# untitled.net
KiCad netlist of a schematic drawn in EAGLE
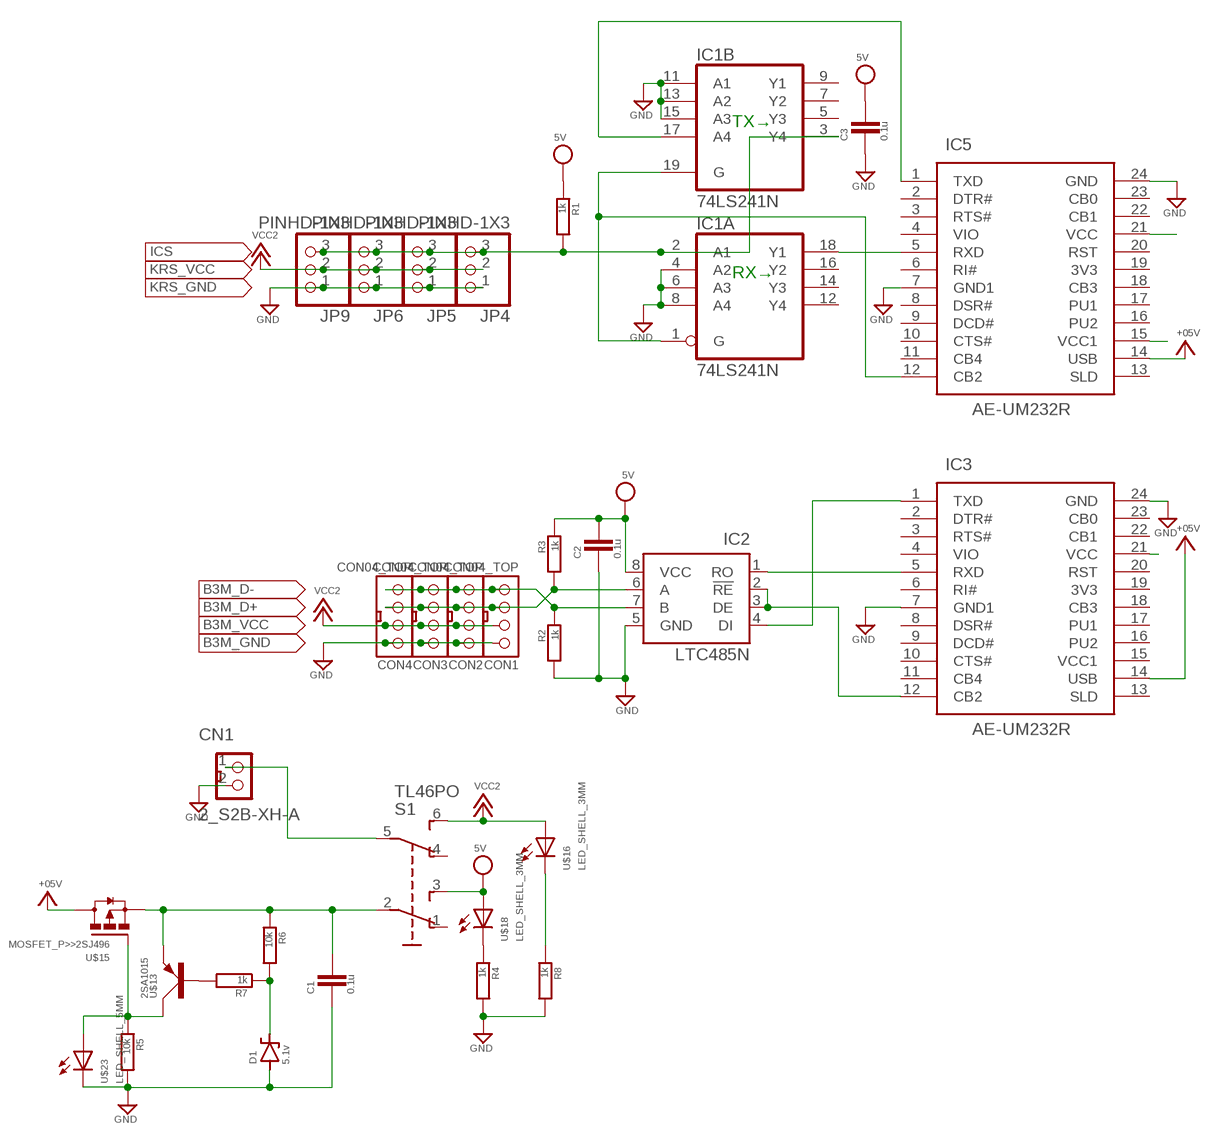
[diagram p0: schematic, sheet 1]

(export (version "E")
  (design (tool "Eeschema 10.0.6"))
  (components
    (comp (ref "C1")
      (value "0.1u")
      (footprint "eagle-import:C050-024X044")
      (libsource (lib "eagle-import") (part "C{gt}{gt}050-024X044"))
    )
    (comp (ref "C2")
      (value "0.1u")
      (footprint "eagle-import:C050-024X044")
      (libsource (lib "eagle-import") (part "C{gt}{gt}050-024X044"))
    )
    (comp (ref "C3")
      (value "0.1u")
      (footprint "eagle-import:C050-024X044")
      (libsource (lib "eagle-import") (part "C{gt}{gt}050-024X044"))
    )
    (comp (ref "CN1")
      (value "2_S2B-XH-A")
      (footprint "eagle-import:S2B-XH-A")
      (libsource (lib "eagle-import") (part "2_S2B-XH-A"))
    )
    (comp (ref "CON1")
      (value "CON04_TOP")
      (footprint "eagle-import:TOP_CON4")
      (libsource (lib "eagle-import") (part "CON04_TOP"))
    )
    (comp (ref "CON2")
      (value "CON04_TOP")
      (footprint "eagle-import:TOP_CON4")
      (libsource (lib "eagle-import") (part "CON04_TOP"))
    )
    (comp (ref "CON3")
      (value "CON04_TOP")
      (footprint "eagle-import:TOP_CON4")
      (libsource (lib "eagle-import") (part "CON04_TOP"))
    )
    (comp (ref "CON4")
      (value "CON04_TOP")
      (footprint "eagle-import:TOP_CON4")
      (libsource (lib "eagle-import") (part "CON04_TOP"))
    )
    (comp (ref "D1")
      (value "5.1v")
      (footprint "eagle-import:ZDIO-5")
      (libsource (lib "eagle-import") (part "ZENER-DIODE{gt}{gt}ZD-5"))
    )
    (comp (ref "IC1")
      (value "74LS241N")
      (footprint "eagle-import:DIL20")
      (libsource (lib "eagle-import") (part "74241NLS"))
    )
    (comp (ref "IC2")
      (value "LTC485N")
      (footprint "eagle-import:DIL08")
      (libsource (lib "eagle-import") (part "LTC485N"))
    )
    (comp (ref "IC3")
      (value "AE-UM232R")
      (footprint "eagle-import:AE-UM232R")
      (libsource (lib "eagle-import") (part "AE-UM232R"))
    )
    (comp (ref "IC5")
      (value "AE-UM232R")
      (footprint "eagle-import:AE-UM232R")
      (libsource (lib "eagle-import") (part "AE-UM232R"))
    )
    (comp (ref "JP4")
      (value "PINHD-1X3")
      (footprint "eagle-import:1X03")
      (libsource (lib "eagle-import") (part "PINHD-1X3"))
    )
    (comp (ref "JP5")
      (value "PINHD-1X3")
      (footprint "eagle-import:1X03")
      (libsource (lib "eagle-import") (part "PINHD-1X3"))
    )
    (comp (ref "JP6")
      (value "PINHD-1X3")
      (footprint "eagle-import:1X03")
      (libsource (lib "eagle-import") (part "PINHD-1X3"))
    )
    (comp (ref "JP9")
      (value "PINHD-1X3")
      (footprint "eagle-import:1X03")
      (libsource (lib "eagle-import") (part "PINHD-1X3"))
    )
    (comp (ref "R1")
      (value "1k")
      (footprint "eagle-import:1_4W(8MM)")
      (libsource (lib "eagle-import") (part "R-EU{gt}{gt}1/4W(8MM)"))
    )
    (comp (ref "R2")
      (value "1k")
      (footprint "eagle-import:1_4W(8MM)")
      (libsource (lib "eagle-import") (part "R-EU{gt}{gt}1/4W(8MM)"))
    )
    (comp (ref "R3")
      (value "1k")
      (footprint "eagle-import:1_4W(8MM)")
      (libsource (lib "eagle-import") (part "R-EU{gt}{gt}1/4W(8MM)"))
    )
    (comp (ref "R4")
      (value "1k")
      (footprint "eagle-import:1_4W(8MM)")
      (libsource (lib "eagle-import") (part "R-EU{gt}{gt}1/4W(8MM)"))
    )
    (comp (ref "R5")
      (value "10k")
      (footprint "eagle-import:1_4W(8MM)")
      (libsource (lib "eagle-import") (part "R-EU{gt}{gt}1/4W(8MM)"))
    )
    (comp (ref "R6")
      (value "10k")
      (footprint "eagle-import:1_4W(8MM)")
      (libsource (lib "eagle-import") (part "R-EU{gt}{gt}1/4W(8MM)"))
    )
    (comp (ref "R7")
      (value "1k")
      (footprint "eagle-import:1_4W(8MM)")
      (libsource (lib "eagle-import") (part "R-EU{gt}{gt}1/4W(8MM)"))
    )
    (comp (ref "R8")
      (value "1k")
      (footprint "eagle-import:1_4W(8MM)")
      (libsource (lib "eagle-import") (part "R-EU{gt}{gt}1/4W(8MM)"))
    )
    (comp (ref "S1")
      (value "TL46PO")
      (footprint "eagle-import:TL4XPO")
      (libsource (lib "eagle-import") (part "TL46PO"))
    )
    (comp (ref "U$13")
      (value "2SA1015")
      (footprint "eagle-import:TO-92")
      (libsource (lib "eagle-import") (part "TR_PNP{gt}{gt}TO-92"))
    )
    (comp (ref "U$15")
      (value "MOSFET_P>>2SJ496")
      (footprint "eagle-import:TO-92")
      (libsource (lib "eagle-import") (part "MOSFET_P{gt}{gt}2SJ496"))
    )
    (comp (ref "U$16")
      (value "LED_SHELL_3MM")
      (footprint "eagle-import:3MM")
      (libsource (lib "eagle-import") (part "LED_SHELL_3MM"))
    )
    (comp (ref "U$18")
      (value "LED_SHELL_3MM")
      (footprint "eagle-import:3MM")
      (libsource (lib "eagle-import") (part "LED_SHELL_3MM"))
    )
    (comp (ref "U$23")
      (value "LED_SHELL_5MM")
      (footprint "eagle-import:5MM")
      (libsource (lib "eagle-import") (part "LED_SHELL_5MM"))
    )
  )
  (nets
    (net (code "1") (name "+05V") (class "Default")
      (node (ref "IC3") (pin "14") (pinfunction "USB_14") (pintype "bidirectional"))
      (node (ref "IC5") (pin "14") (pinfunction "USB_14") (pintype "bidirectional"))
      (node (ref "U$15") (pin "2") (pinfunction "D_2") (pintype "passive"))
    )
    (net (code "2") (name "/VCC1") (class "Default")
      (node (ref "IC3") (pin "15") (pinfunction "VCC1_15") (pintype "power_in"))
    )
    (net (code "3") (name "5V") (class "Default")
      (node (ref "C2") (pin "1") (pinfunction "1_1") (pintype "passive"))
      (node (ref "C3") (pin "1") (pinfunction "1_1") (pintype "passive"))
      (node (ref "IC2") (pin "8") (pinfunction "VCC_8") (pintype "input"))
      (node (ref "R1") (pin "1") (pinfunction "1_1") (pintype "passive"))
      (node (ref "R3") (pin "1") (pinfunction "1_1") (pintype "passive"))
      (node (ref "S1") (pin "3") (pinfunction "S_3") (pintype "passive"))
      (node (ref "U$18") (pin "P$1") (pinfunction "A_P$1") (pintype "passive"))
    )
    (net (code "4") (name "GND") (class "Default")
      (node (ref "C1") (pin "2") (pinfunction "2_2") (pintype "passive"))
      (node (ref "C2") (pin "2") (pinfunction "2_2") (pintype "passive"))
      (node (ref "C3") (pin "2") (pinfunction "2_2") (pintype "passive"))
      (node (ref "CN1") (pin "2") (pinfunction "2_2") (pintype "passive"))
      (node (ref "CON1") (pin "P$1") (pinfunction "1_P$1") (pintype "bidirectional"))
      (node (ref "CON2") (pin "P$1") (pinfunction "1_P$1") (pintype "bidirectional"))
      (node (ref "CON3") (pin "P$1") (pinfunction "1_P$1") (pintype "bidirectional"))
      (node (ref "CON4") (pin "P$1") (pinfunction "1_P$1") (pintype "bidirectional"))
      (node (ref "D1") (pin "A") (pinfunction "A_A") (pintype "passive"))
      (node (ref "IC1") (pin "11") (pinfunction "A1_11") (pintype "input"))
      (node (ref "IC1") (pin "13") (pinfunction "A2_13") (pintype "input"))
      (node (ref "IC1") (pin "15") (pinfunction "A3_15") (pintype "input"))
      (node (ref "IC1") (pin "4") (pinfunction "A2_4") (pintype "input"))
      (node (ref "IC1") (pin "6") (pinfunction "A3_6") (pintype "input"))
      (node (ref "IC1") (pin "8") (pinfunction "A4_8") (pintype "input"))
      (node (ref "IC2") (pin "5") (pinfunction "GND_5") (pintype "input"))
      (node (ref "IC3") (pin "24") (pinfunction "GND_24") (pintype "power_in"))
      (node (ref "IC3") (pin "7") (pinfunction "GND1_7") (pintype "power_in"))
      (node (ref "IC5") (pin "24") (pinfunction "GND_24") (pintype "power_in"))
      (node (ref "IC5") (pin "7") (pinfunction "GND1_7") (pintype "power_in"))
      (node (ref "JP4") (pin "1") (pinfunction "1_1") (pintype "passive"))
      (node (ref "JP5") (pin "1") (pinfunction "1_1") (pintype "passive"))
      (node (ref "JP6") (pin "1") (pinfunction "1_1") (pintype "passive"))
      (node (ref "JP9") (pin "1") (pinfunction "1_1") (pintype "passive"))
      (node (ref "R2") (pin "2") (pinfunction "2_2") (pintype "passive"))
      (node (ref "R4") (pin "2") (pinfunction "2_2") (pintype "passive"))
      (node (ref "R5") (pin "2") (pinfunction "2_2") (pintype "passive"))
      (node (ref "R8") (pin "2") (pinfunction "2_2") (pintype "passive"))
      (node (ref "U$23") (pin "P$2") (pinfunction "C_P$2") (pintype "passive"))
    )
    (net (code "5") (name "Net-(CON1-3)") (class "Default")
      (node (ref "CON1") (pin "P$3") (pinfunction "3_P$3") (pintype "bidirectional"))
      (node (ref "CON2") (pin "P$3") (pinfunction "3_P$3") (pintype "bidirectional"))
      (node (ref "CON3") (pin "P$3") (pinfunction "3_P$3") (pintype "bidirectional"))
      (node (ref "CON4") (pin "P$3") (pinfunction "3_P$3") (pintype "bidirectional"))
      (node (ref "IC2") (pin "6") (pinfunction "A_6") (pintype "bidirectional"))
      (node (ref "R3") (pin "2") (pinfunction "2_2") (pintype "passive"))
    )
    (net (code "6") (name "Net-(CON1-4)") (class "Default")
      (node (ref "CON1") (pin "P$4") (pinfunction "4_P$4") (pintype "bidirectional"))
      (node (ref "CON2") (pin "P$4") (pinfunction "4_P$4") (pintype "bidirectional"))
      (node (ref "CON3") (pin "P$4") (pinfunction "4_P$4") (pintype "bidirectional"))
      (node (ref "CON4") (pin "P$4") (pinfunction "4_P$4") (pintype "bidirectional"))
      (node (ref "IC2") (pin "7") (pinfunction "B_7") (pintype "bidirectional"))
      (node (ref "R2") (pin "1") (pinfunction "1_1") (pintype "passive"))
    )
    (net (code "7") (name "Net-(D1-PadC)") (class "Default")
      (node (ref "D1") (pin "C") (pinfunction "C_C") (pintype "passive"))
      (node (ref "R6") (pin "2") (pinfunction "2_2") (pintype "passive"))
      (node (ref "R7") (pin "1") (pinfunction "1_1") (pintype "passive"))
    )
    (net (code "8") (name "Net-(IC1A-A1)") (class "Default")
      (node (ref "IC1") (pin "2") (pinfunction "A1_2") (pintype "input"))
      (node (ref "IC1") (pin "3") (pinfunction "Y4_3") (pintype "tri_state"))
      (node (ref "JP4") (pin "3") (pinfunction "3_3") (pintype "passive"))
      (node (ref "JP5") (pin "3") (pinfunction "3_3") (pintype "passive"))
      (node (ref "JP6") (pin "3") (pinfunction "3_3") (pintype "passive"))
      (node (ref "JP9") (pin "3") (pinfunction "3_3") (pintype "passive"))
      (node (ref "R1") (pin "2") (pinfunction "2_2") (pintype "passive"))
    )
    (net (code "9") (name "Net-(IC1A-G)") (class "Default")
      (node (ref "IC1") (pin "1") (pinfunction "G_1") (pintype "input"))
      (node (ref "IC1") (pin "19") (pinfunction "G_19") (pintype "input"))
      (node (ref "IC5") (pin "12") (pinfunction "CB2_12") (pintype "bidirectional"))
    )
    (net (code "10") (name "Net-(IC1A-Y1)") (class "Default")
      (node (ref "IC1") (pin "18") (pinfunction "Y1_18") (pintype "tri_state"))
      (node (ref "IC5") (pin "5") (pinfunction "RXD_5") (pintype "bidirectional"))
    )
    (net (code "11") (name "Net-(IC1B-A4)") (class "Default")
      (node (ref "IC1") (pin "17") (pinfunction "A4_17") (pintype "input"))
      (node (ref "IC5") (pin "1") (pinfunction "TXD_1") (pintype "bidirectional"))
    )
    (net (code "12") (name "Net-(IC2-DE)") (class "Default")
      (node (ref "IC2") (pin "2") (pinfunction "~{RE}_2") (pintype "input"))
      (node (ref "IC2") (pin "3") (pinfunction "DE_3") (pintype "input"))
      (node (ref "IC3") (pin "12") (pinfunction "CB2_12") (pintype "bidirectional"))
    )
    (net (code "13") (name "Net-(IC2-DI)") (class "Default")
      (node (ref "IC2") (pin "4") (pinfunction "DI_4") (pintype "input"))
      (node (ref "IC3") (pin "1") (pinfunction "TXD_1") (pintype "bidirectional"))
    )
    (net (code "14") (name "Net-(IC2-RO)") (class "Default")
      (node (ref "IC2") (pin "1") (pinfunction "RO_1") (pintype "output"))
      (node (ref "IC3") (pin "5") (pinfunction "RXD_5") (pintype "bidirectional"))
    )
    (net (code "15") (name "Net-(S1-P)") (class "Default")
      (node (ref "C1") (pin "1") (pinfunction "1_1") (pintype "passive"))
      (node (ref "R6") (pin "1") (pinfunction "1_1") (pintype "passive"))
      (node (ref "S1") (pin "2") (pinfunction "P_2") (pintype "passive"))
      (node (ref "U$13") (pin "1") (pinfunction "E_1") (pintype "passive"))
      (node (ref "U$15") (pin "1") (pinfunction "S_1") (pintype "passive"))
    )
    (net (code "16") (name "Net-(S1-P1)") (class "Default")
      (node (ref "CN1") (pin "1") (pinfunction "1_1") (pintype "passive"))
      (node (ref "S1") (pin "5") (pinfunction "P1_5") (pintype "passive"))
    )
    (net (code "17") (name "Net-(U$13-B)") (class "Default")
      (node (ref "R7") (pin "2") (pinfunction "2_2") (pintype "passive"))
      (node (ref "U$13") (pin "3") (pinfunction "B_3") (pintype "passive"))
    )
    (net (code "18") (name "Net-(U$13-C)") (class "Default")
      (node (ref "R5") (pin "1") (pinfunction "1_1") (pintype "passive"))
      (node (ref "U$13") (pin "2") (pinfunction "C_2") (pintype "passive"))
      (node (ref "U$15") (pin "3") (pinfunction "G_3") (pintype "passive"))
      (node (ref "U$23") (pin "P$1") (pinfunction "A_P$1") (pintype "passive"))
    )
    (net (code "19") (name "Net-(U$16-C)") (class "Default")
      (node (ref "R8") (pin "1") (pinfunction "1_1") (pintype "passive"))
      (node (ref "U$16") (pin "P$2") (pinfunction "C_P$2") (pintype "passive"))
    )
    (net (code "20") (name "Net-(U$18-C)") (class "Default")
      (node (ref "R4") (pin "1") (pinfunction "1_1") (pintype "passive"))
      (node (ref "U$18") (pin "P$2") (pinfunction "C_P$2") (pintype "passive"))
    )
    (net (code "21") (name "VCC2") (class "Default")
      (node (ref "CON1") (pin "P$2") (pinfunction "2_P$2") (pintype "bidirectional"))
      (node (ref "CON2") (pin "P$2") (pinfunction "2_P$2") (pintype "bidirectional"))
      (node (ref "CON3") (pin "P$2") (pinfunction "2_P$2") (pintype "bidirectional"))
      (node (ref "CON4") (pin "P$2") (pinfunction "2_P$2") (pintype "bidirectional"))
      (node (ref "JP4") (pin "2") (pinfunction "2_2") (pintype "passive"))
      (node (ref "JP5") (pin "2") (pinfunction "2_2") (pintype "passive"))
      (node (ref "JP6") (pin "2") (pinfunction "2_2") (pintype "passive"))
      (node (ref "JP9") (pin "2") (pinfunction "2_2") (pintype "passive"))
      (node (ref "S1") (pin "6") (pinfunction "S1_6") (pintype "passive"))
      (node (ref "U$16") (pin "P$1") (pinfunction "A_P$1") (pintype "passive"))
    )
    (net (code "22") (name "unconnected-(IC1A-Y2-Pad16)") (class "Default")
      (node (ref "IC1") (pin "16") (pinfunction "Y2_16") (pintype "tri_state"))
    )
    (net (code "23") (name "unconnected-(IC1A-Y3-Pad14)") (class "Default")
      (node (ref "IC1") (pin "14") (pinfunction "Y3_14") (pintype "tri_state"))
    )
    (net (code "24") (name "unconnected-(IC1A-Y4-Pad12)") (class "Default")
      (node (ref "IC1") (pin "12") (pinfunction "Y4_12") (pintype "tri_state"))
    )
    (net (code "25") (name "unconnected-(IC1B-Y1-Pad9)") (class "Default")
      (node (ref "IC1") (pin "9") (pinfunction "Y1_9") (pintype "tri_state"))
    )
    (net (code "26") (name "unconnected-(IC1B-Y2-Pad7)") (class "Default")
      (node (ref "IC1") (pin "7") (pinfunction "Y2_7") (pintype "tri_state"))
    )
    (net (code "27") (name "unconnected-(IC1B-Y3-Pad5)") (class "Default")
      (node (ref "IC1") (pin "5") (pinfunction "Y3_5") (pintype "tri_state"))
    )
    (net (code "28") (name "unconnected-(IC3-3V3-Pad19)") (class "Default")
      (node (ref "IC3") (pin "19") (pinfunction "3V3_19") (pintype "bidirectional"))
    )
    (net (code "29") (name "unconnected-(IC3-CB0-Pad23)") (class "Default")
      (node (ref "IC3") (pin "23") (pinfunction "CB0_23") (pintype "bidirectional"))
    )
    (net (code "30") (name "unconnected-(IC3-CB1-Pad22)") (class "Default")
      (node (ref "IC3") (pin "22") (pinfunction "CB1_22") (pintype "bidirectional"))
    )
    (net (code "31") (name "unconnected-(IC3-CB3-Pad18)") (class "Default")
      (node (ref "IC3") (pin "18") (pinfunction "CB3_18") (pintype "bidirectional"))
    )
    (net (code "32") (name "unconnected-(IC3-CB4-Pad11)") (class "Default")
      (node (ref "IC3") (pin "11") (pinfunction "CB4_11") (pintype "bidirectional"))
    )
    (net (code "33") (name "unconnected-(IC3-CTS#-Pad10)") (class "Default")
      (node (ref "IC3") (pin "10") (pinfunction "CTS#_10") (pintype "bidirectional"))
    )
    (net (code "34") (name "unconnected-(IC3-DCD#-Pad9)") (class "Default")
      (node (ref "IC3") (pin "9") (pinfunction "DCD#_9") (pintype "bidirectional"))
    )
    (net (code "35") (name "unconnected-(IC3-DSR#-Pad8)") (class "Default")
      (node (ref "IC3") (pin "8") (pinfunction "DSR#_8") (pintype "bidirectional"))
    )
    (net (code "36") (name "unconnected-(IC3-DTR#-Pad2)") (class "Default")
      (node (ref "IC3") (pin "2") (pinfunction "DTR#_2") (pintype "bidirectional"))
    )
    (net (code "37") (name "unconnected-(IC3-PU1-Pad17)") (class "Default")
      (node (ref "IC3") (pin "17") (pinfunction "PU1_17") (pintype "bidirectional"))
    )
    (net (code "38") (name "unconnected-(IC3-PU2-Pad16)") (class "Default")
      (node (ref "IC3") (pin "16") (pinfunction "PU2_16") (pintype "bidirectional"))
    )
    (net (code "39") (name "unconnected-(IC3-RI#-Pad6)") (class "Default")
      (node (ref "IC3") (pin "6") (pinfunction "RI#_6") (pintype "bidirectional"))
    )
    (net (code "40") (name "unconnected-(IC3-RST-Pad20)") (class "Default")
      (node (ref "IC3") (pin "20") (pinfunction "RST_20") (pintype "bidirectional"))
    )
    (net (code "41") (name "unconnected-(IC3-RTS#-Pad3)") (class "Default")
      (node (ref "IC3") (pin "3") (pinfunction "RTS#_3") (pintype "bidirectional"))
    )
    (net (code "42") (name "unconnected-(IC3-SLD-Pad13)") (class "Default")
      (node (ref "IC3") (pin "13") (pinfunction "SLD_13") (pintype "bidirectional"))
    )
    (net (code "43") (name "unconnected-(IC3-VCC-Pad21)") (class "Default")
      (node (ref "IC3") (pin "21") (pinfunction "VCC_21") (pintype "power_in"))
    )
    (net (code "44") (name "unconnected-(IC3-VIO-Pad4)") (class "Default")
      (node (ref "IC3") (pin "4") (pinfunction "VIO_4") (pintype "bidirectional"))
    )
    (net (code "45") (name "unconnected-(IC5-3V3-Pad19)") (class "Default")
      (node (ref "IC5") (pin "19") (pinfunction "3V3_19") (pintype "bidirectional"))
    )
    (net (code "46") (name "unconnected-(IC5-CB0-Pad23)") (class "Default")
      (node (ref "IC5") (pin "23") (pinfunction "CB0_23") (pintype "bidirectional"))
    )
    (net (code "47") (name "unconnected-(IC5-CB1-Pad22)") (class "Default")
      (node (ref "IC5") (pin "22") (pinfunction "CB1_22") (pintype "bidirectional"))
    )
    (net (code "48") (name "unconnected-(IC5-CB3-Pad18)") (class "Default")
      (node (ref "IC5") (pin "18") (pinfunction "CB3_18") (pintype "bidirectional"))
    )
    (net (code "49") (name "unconnected-(IC5-CB4-Pad11)") (class "Default")
      (node (ref "IC5") (pin "11") (pinfunction "CB4_11") (pintype "bidirectional"))
    )
    (net (code "50") (name "unconnected-(IC5-CTS#-Pad10)") (class "Default")
      (node (ref "IC5") (pin "10") (pinfunction "CTS#_10") (pintype "bidirectional"))
    )
    (net (code "51") (name "unconnected-(IC5-DCD#-Pad9)") (class "Default")
      (node (ref "IC5") (pin "9") (pinfunction "DCD#_9") (pintype "bidirectional"))
    )
    (net (code "52") (name "unconnected-(IC5-DSR#-Pad8)") (class "Default")
      (node (ref "IC5") (pin "8") (pinfunction "DSR#_8") (pintype "bidirectional"))
    )
    (net (code "53") (name "unconnected-(IC5-DTR#-Pad2)") (class "Default")
      (node (ref "IC5") (pin "2") (pinfunction "DTR#_2") (pintype "bidirectional"))
    )
    (net (code "54") (name "unconnected-(IC5-PU1-Pad17)") (class "Default")
      (node (ref "IC5") (pin "17") (pinfunction "PU1_17") (pintype "bidirectional"))
    )
    (net (code "55") (name "unconnected-(IC5-PU2-Pad16)") (class "Default")
      (node (ref "IC5") (pin "16") (pinfunction "PU2_16") (pintype "bidirectional"))
    )
    (net (code "56") (name "unconnected-(IC5-RI#-Pad6)") (class "Default")
      (node (ref "IC5") (pin "6") (pinfunction "RI#_6") (pintype "bidirectional"))
    )
    (net (code "57") (name "unconnected-(IC5-RST-Pad20)") (class "Default")
      (node (ref "IC5") (pin "20") (pinfunction "RST_20") (pintype "bidirectional"))
    )
    (net (code "58") (name "unconnected-(IC5-RTS#-Pad3)") (class "Default")
      (node (ref "IC5") (pin "3") (pinfunction "RTS#_3") (pintype "bidirectional"))
    )
    (net (code "59") (name "unconnected-(IC5-SLD-Pad13)") (class "Default")
      (node (ref "IC5") (pin "13") (pinfunction "SLD_13") (pintype "bidirectional"))
    )
    (net (code "60") (name "unconnected-(IC5-VCC-Pad21)") (class "Default")
      (node (ref "IC5") (pin "21") (pinfunction "VCC_21") (pintype "power_in"))
    )
    (net (code "61") (name "unconnected-(IC5-VCC1-Pad15)") (class "Default")
      (node (ref "IC5") (pin "15") (pinfunction "VCC1_15") (pintype "power_in"))
    )
    (net (code "62") (name "unconnected-(IC5-VIO-Pad4)") (class "Default")
      (node (ref "IC5") (pin "4") (pinfunction "VIO_4") (pintype "bidirectional"))
    )
    (net (code "63") (name "unconnected-(S1-O-Pad1)") (class "Default")
      (node (ref "S1") (pin "1") (pinfunction "O_1") (pintype "passive"))
    )
    (net (code "64") (name "unconnected-(S1-O1-Pad4)") (class "Default")
      (node (ref "S1") (pin "4") (pinfunction "O1_4") (pintype "passive"))
    )
  )
)
